# boxer_rpi.net
KiCad netlist of a schematic drawn in Altium Designer
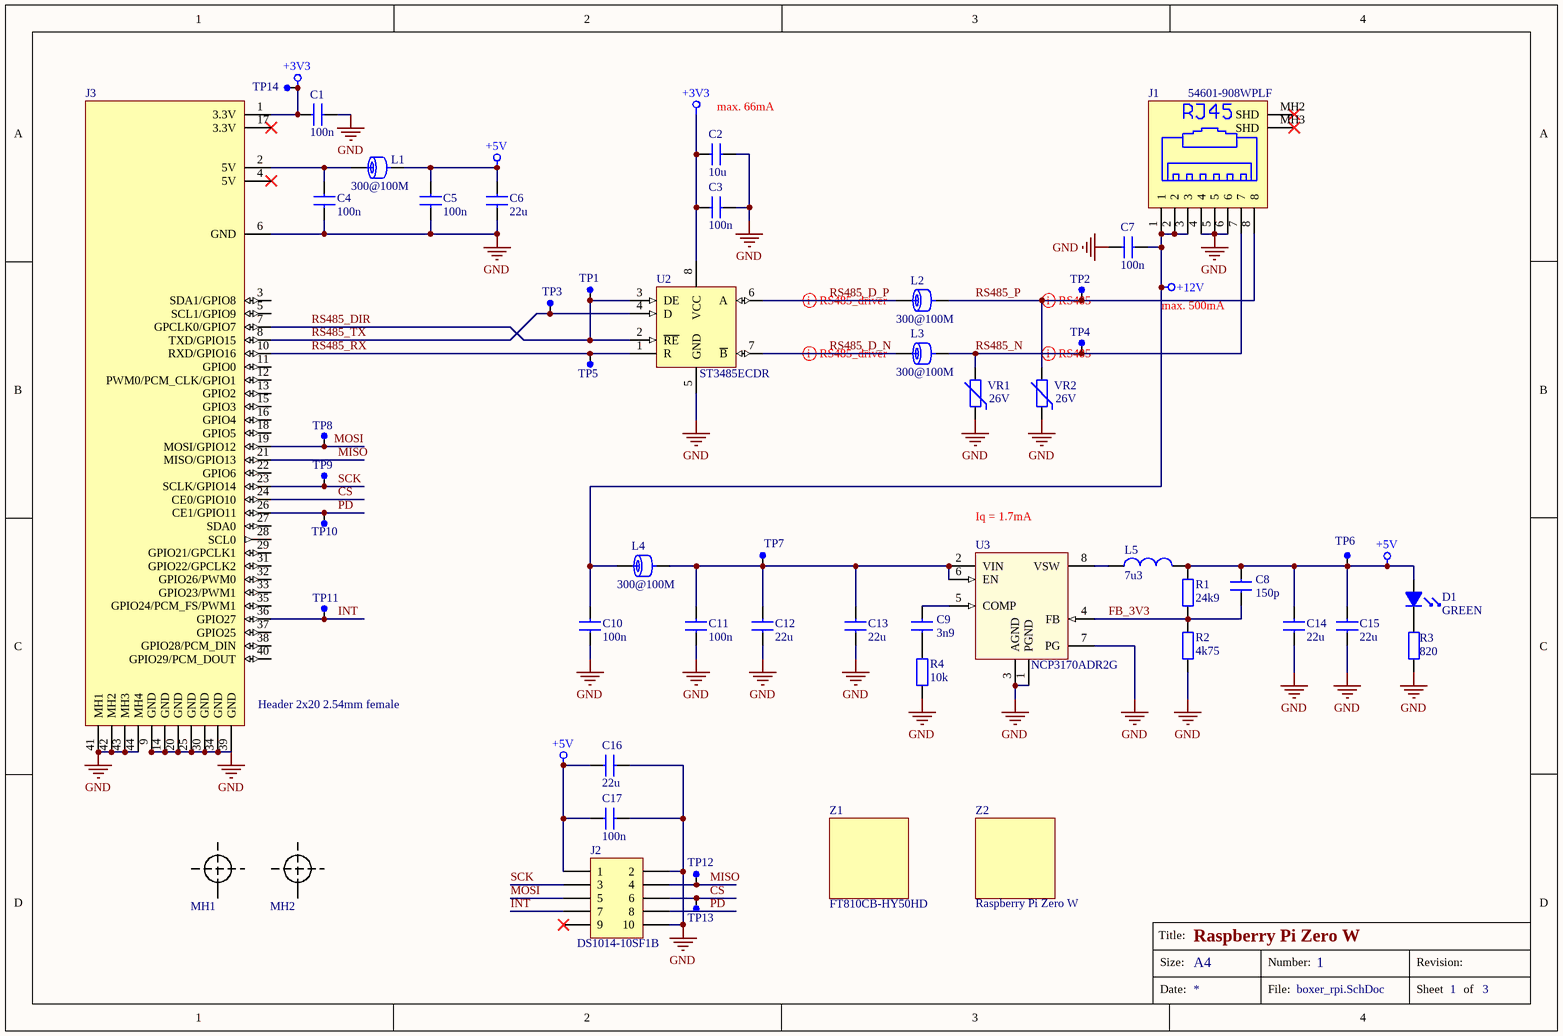
[diagram p0: boxer_rpi.SchDoc]

(export (version "E")
  (design (tool "Eeschema 10.0.6"))
  (components
    (comp (ref "C1")
      (value "100n")
      (footprint "C_0805")
      (description "Capacitor")
      (libsource (lib "boxer_pas") (part "Capacitor"))
    )
    (comp (ref "C2")
      (value "10u")
      (footprint "C_1206")
      (description "Capacitor")
      (fields (field (name "Comment") "TME: CL31A226MOCLNNC"))
      (libsource (lib "boxer_pas") (part "Capacitor"))
    )
    (comp (ref "C3")
      (value "100n")
      (footprint "C_0805")
      (description "Capacitor")
      (libsource (lib "boxer_pas") (part "Capacitor"))
    )
    (comp (ref "C4")
      (value "100n")
      (footprint "C_0805")
      (description "Capacitor")
      (libsource (lib "boxer_pas") (part "Capacitor"))
    )
    (comp (ref "C5")
      (value "100n")
      (footprint "C_0805")
      (description "Capacitor")
      (libsource (lib "boxer_pas") (part "Capacitor"))
    )
    (comp (ref "C6")
      (value "22u")
      (footprint "C_1206")
      (description "Capacitor")
      (fields (field (name "Comment") "TME: CL31A226MOCLNNC"))
      (libsource (lib "boxer_pas") (part "Capacitor"))
    )
    (comp (ref "C7")
      (value "100n")
      (footprint "C_0805")
      (description "Capacitor")
      (libsource (lib "boxer_pas") (part "Capacitor"))
    )
    (comp (ref "C8")
      (value "150p")
      (footprint "C_0805")
      (description "Capacitor")
      (fields (field (name "Comment") "885012207081"))
      (libsource (lib "boxer_pas") (part "Capacitor"))
    )
    (comp (ref "C9")
      (value "3n9")
      (footprint "C_0805")
      (description "Capacitor")
      (fields (field (name "Comment") "885012207089"))
      (libsource (lib "boxer_pas") (part "Capacitor"))
    )
    (comp (ref "C10")
      (value "100n")
      (footprint "C_0805")
      (description "Capacitor")
      (libsource (lib "boxer_pas") (part "Capacitor"))
    )
    (comp (ref "C11")
      (value "100n")
      (footprint "C_0805")
      (description "Capacitor")
      (libsource (lib "boxer_pas") (part "Capacitor"))
    )
    (comp (ref "C12")
      (value "22u")
      (footprint "C_1206")
      (description "Capacitor")
      (fields (field (name "Comment") "TME: CL31A226MOCLNNC"))
      (libsource (lib "boxer_pas") (part "Capacitor"))
    )
    (comp (ref "C13")
      (value "22u")
      (footprint "C_1206")
      (description "Capacitor")
      (fields (field (name "Comment") "TME: CL31A226MOCLNNC"))
      (libsource (lib "boxer_pas") (part "Capacitor"))
    )
    (comp (ref "C14")
      (value "22u")
      (footprint "C_1206")
      (description "Capacitor")
      (fields (field (name "Comment") "TME: CL31A226MOCLNNC"))
      (libsource (lib "boxer_pas") (part "Capacitor"))
    )
    (comp (ref "C15")
      (value "22u")
      (footprint "C_1206")
      (description "Capacitor")
      (fields (field (name "Comment") "TME: CL31A226MOCLNNC"))
      (libsource (lib "boxer_pas") (part "Capacitor"))
    )
    (comp (ref "C16")
      (value "22u")
      (footprint "C_1206")
      (description "Capacitor")
      (fields (field (name "Comment") "TME: CL31A226MOCLNNC"))
      (libsource (lib "boxer_pas") (part "Capacitor"))
    )
    (comp (ref "C17")
      (value "100n")
      (footprint "C_0805")
      (description "Capacitor")
      (libsource (lib "boxer_pas") (part "Capacitor"))
    )
    (comp (ref "D1")
      (value "GREEN")
      (footprint "LED_0805")
      (description "Typical RED, GREEN, YELLOW, AMBER GaAs LED")
      (fields (field (name "Comment") "KP-2012LSGC"))
      (libsource (lib "altium-import") (part "root_3_LED_"))
    )
    (comp (ref "J1")
      (value "54601-908WPLF")
      (footprint "RJ45_54601-908WPLF")
      (description "RJ45 Socket, 8pin, No Key, Molex MX-95001-2881")
      (libsource (lib "boxer_mechanical") (part "RJ45-8"))
    )
    (comp (ref "J2")
      (value "DS1014-10SF1B")
      (footprint "215307-5")
      (description "Header, 5-Pin, Dual row")
      (fields (field (name "Comment") "Header 5X2"))
      (libsource (lib "boxer_mechanical") (part "Header 5X2"))
    )
    (comp (ref "J3")
      (value "Header 2x20 2.54mm female")
      (footprint "Header RPI0")
      (fields (field (name "Comment") "Header RPi Zero W"))
      (libsource (lib "boxer_mechanical") (part "Header RPI0"))
    )
    (comp (ref "L1")
      (value "300@100M")
      (footprint "L_0805")
      (description "Ferrite Bead")
      (fields (field (name "Comment") "742792031"))
      (libsource (lib "boxer_pas") (part "FB"))
    )
    (comp (ref "L2")
      (value "300@100M")
      (footprint "L_0805")
      (description "Ferrite Bead")
      (fields (field (name "Comment") "742792031"))
      (libsource (lib "boxer_pas") (part "FB"))
    )
    (comp (ref "L3")
      (value "300@100M")
      (footprint "L_0805")
      (description "Ferrite Bead")
      (fields (field (name "Comment") "742792031"))
      (libsource (lib "boxer_pas") (part "FB"))
    )
    (comp (ref "L4")
      (value "300@100M")
      (footprint "L_0805")
      (description "Ferrite Bead")
      (fields (field (name "Comment") "742792031"))
      (libsource (lib "boxer_pas") (part "FB"))
    )
    (comp (ref "L5")
      (value "7u3")
      (footprint "L_6.7x6.7mm")
      (description "FIXED IND 7.3UH 2.1A 54 MOHM SMD")
      (fields (field (name "Comment") "308-1500-1-ND"))
      (libsource (lib "boxer_pas") (part "Inductor"))
    )
    (comp (ref "MH1")
      (value "Mounting hole")
      (footprint "MH_M3")
      (libsource (lib "boxer_mechanical") (part "Mounting hole"))
    )
    (comp (ref "MH2")
      (value "Mounting hole")
      (footprint "MH_M3")
      (libsource (lib "boxer_mechanical") (part "Mounting hole"))
    )
    (comp (ref "R1")
      (value "24k9")
      (footprint "R_0805")
      (description "Resistor")
      (fields (field (name "Comment") "RNCP0805FTD24K9"))
      (libsource (lib "boxer_pas") (part "Resistor"))
    )
    (comp (ref "R2")
      (value "4k75")
      (footprint "R_0805")
      (description "Resistor")
      (fields (field (name "Comment") "RNCP0805FTD4K75"))
      (libsource (lib "boxer_pas") (part "Resistor"))
    )
    (comp (ref "R3")
      (value "820")
      (footprint "R_0805")
      (description "Resistor")
      (libsource (lib "altium-import") (part "root_1_Resistor_"))
    )
    (comp (ref "R4")
      (value "10k")
      (footprint "R_1206")
      (description "Resistor")
      (libsource (lib "boxer_pas") (part "Resistor"))
    )
    (comp (ref "TP1")
      (value "TEST PAD")
      (footprint "PIN")
      (description "PAD 1.5mm")
      (libsource (lib "boxer_mechanical") (part "TEST_PAD"))
    )
    (comp (ref "TP2")
      (value "TEST PAD")
      (footprint "PIN")
      (description "PAD 1.5mm")
      (libsource (lib "boxer_mechanical") (part "TEST_PAD"))
    )
    (comp (ref "TP3")
      (value "TEST PAD")
      (footprint "PIN")
      (description "PAD 1.5mm")
      (libsource (lib "boxer_mechanical") (part "TEST_PAD"))
    )
    (comp (ref "TP4")
      (value "TEST PAD")
      (footprint "PIN")
      (description "PAD 1.5mm")
      (libsource (lib "boxer_mechanical") (part "TEST_PAD"))
    )
    (comp (ref "TP5")
      (value "TEST PAD")
      (footprint "PIN")
      (description "PAD 1.5mm")
      (libsource (lib "boxer_mechanical") (part "TEST_PAD"))
    )
    (comp (ref "TP6")
      (value "TEST PAD")
      (footprint "PIN")
      (description "PAD 1.5mm")
      (libsource (lib "boxer_mechanical") (part "TEST_PAD"))
    )
    (comp (ref "TP7")
      (value "TEST PAD")
      (footprint "PIN")
      (description "PAD 1.5mm")
      (libsource (lib "boxer_mechanical") (part "TEST_PAD"))
    )
    (comp (ref "TP8")
      (value "TEST PAD")
      (footprint "PIN")
      (description "PAD 1.5mm")
      (libsource (lib "boxer_mechanical") (part "TEST_PAD"))
    )
    (comp (ref "TP9")
      (value "TEST PAD")
      (footprint "PIN")
      (description "PAD 1.5mm")
      (libsource (lib "boxer_mechanical") (part "TEST_PAD"))
    )
    (comp (ref "TP10")
      (value "TEST PAD")
      (footprint "PIN")
      (description "PAD 1.5mm")
      (libsource (lib "boxer_mechanical") (part "TEST_PAD"))
    )
    (comp (ref "TP11")
      (value "TEST PAD")
      (footprint "PIN")
      (description "PAD 1.5mm")
      (libsource (lib "boxer_mechanical") (part "TEST_PAD"))
    )
    (comp (ref "TP12")
      (value "TEST PAD")
      (footprint "PIN")
      (description "PAD 1.5mm")
      (libsource (lib "boxer_mechanical") (part "TEST_PAD"))
    )
    (comp (ref "TP13")
      (value "TEST PAD")
      (footprint "PIN")
      (description "PAD 1.5mm")
      (libsource (lib "boxer_mechanical") (part "TEST_PAD"))
    )
    (comp (ref "TP14")
      (value "TEST PAD")
      (footprint "PIN")
      (description "PAD 1.5mm")
      (libsource (lib "boxer_mechanical") (part "TEST_PAD"))
    )
    (comp (ref "U2")
      (value "ST3485ECDR")
      (footprint "SO8")
      (description "RS-422/RS-485 Interface IC Hi-Spd Lo Pwr Trans")
      (libsource (lib "boxer_ic") (part "ST485BDR"))
    )
    (comp (ref "U3")
      (value "NCP3170ADR2G")
      (footprint "SO8")
      (description "Synchronous PWM Switching Converter")
      (libsource (lib "boxer_ic") (part "NCP3170"))
    )
    (comp (ref "VR1")
      (value "26V")
      (footprint "VR_0805")
      (description "34.5V 20A Varistor 1 Circuit Surface Mount, MLCV 0805 (2012 Metric)")
      (fields (field (name "Comment") "AMCV-0805-260-C800N-T"))
      (libsource (lib "boxer_pas") (part "Varistor"))
    )
    (comp (ref "VR2")
      (value "26V")
      (footprint "VR_0805")
      (description "34.5V 20A Varistor 1 Circuit Surface Mount, MLCV 0805 (2012 Metric)")
      (fields (field (name "Comment") "AMCV-0805-260-C800N-T"))
      (libsource (lib "boxer_pas") (part "Varistor"))
    )
    (comp (ref "Z1")
      (value "FT810CB-HY50HD")
      (footprint "FT810CB-HY50HD")
      (libsource (lib "boxer_ic") (part "FT810CB-HY50HD"))
    )
    (comp (ref "Z2")
      (value "Raspberry Pi Zero W")
      (footprint "RPI_ZERO")
      (libsource (lib "boxer_ic") (part "RPi Zero W"))
    )
  )
  (nets
    (net (code "1") (name "+3V3") (class "Default")
      (node (ref "C1") (pin "2") (pinfunction "2_2") (pintype "passive"))
      (node (ref "C2") (pin "2") (pinfunction "2_2") (pintype "passive"))
      (node (ref "C3") (pin "1") (pinfunction "1_1") (pintype "passive"))
      (node (ref "J3") (pin "1") (pinfunction "3.3V_1") (pintype "power_in"))
      (node (ref "TP14") (pin "1") (pinfunction "1_1") (pintype "passive"))
      (node (ref "U2") (pin "8") (pinfunction "VCC_8") (pintype "power_in"))
    )
    (net (code "2") (name "+5V") (class "Default")
      (node (ref "C14") (pin "2") (pinfunction "2_2") (pintype "passive"))
      (node (ref "C15") (pin "2") (pinfunction "2_2") (pintype "passive"))
      (node (ref "C16") (pin "2") (pinfunction "2_2") (pintype "passive"))
      (node (ref "C17") (pin "2") (pinfunction "2_2") (pintype "passive"))
      (node (ref "C5") (pin "1") (pinfunction "1_1") (pintype "passive"))
      (node (ref "C6") (pin "2") (pinfunction "2_2") (pintype "passive"))
      (node (ref "C8") (pin "2") (pinfunction "2_2") (pintype "passive"))
      (node (ref "D1") (pin "1") (pinfunction "A_1") (pintype "passive"))
      (node (ref "J2") (pin "1") (pinfunction "1_1") (pintype "passive"))
      (node (ref "L1") (pin "2") (pinfunction "2_2") (pintype "passive"))
      (node (ref "L5") (pin "2") (pinfunction "2_2") (pintype "passive"))
      (node (ref "R1") (pin "2") (pinfunction "2_2") (pintype "passive"))
      (node (ref "TP6") (pin "1") (pinfunction "1_1") (pintype "passive"))
    )
    (net (code "3") (name "+12V") (class "Default")
      (node (ref "C10") (pin "2") (pinfunction "2_2") (pintype "passive"))
      (node (ref "C7") (pin "1") (pinfunction "1_1") (pintype "passive"))
      (node (ref "J1") (pin "1") (pinfunction "1_1") (pintype "passive"))
      (node (ref "J1") (pin "2") (pinfunction "2_2") (pintype "passive"))
      (node (ref "J1") (pin "3") (pinfunction "3_3") (pintype "passive"))
      (node (ref "L4") (pin "1") (pinfunction "1_1") (pintype "passive"))
    )
    (net (code "4") (name "/CS") (class "Default")
      (node (ref "J2") (pin "6") (pinfunction "6_6") (pintype "passive"))
      (node (ref "J3") (pin "24") (pinfunction "CE0/GPIO10_24") (pintype "bidirectional"))
      (node (ref "TP13") (pin "1") (pinfunction "1_1") (pintype "passive"))
    )
    (net (code "5") (name "/FB_3V3") (class "Default")
      (node (ref "C8") (pin "1") (pinfunction "1_1") (pintype "passive"))
      (node (ref "R1") (pin "1") (pinfunction "1_1") (pintype "passive"))
      (node (ref "R2") (pin "2") (pinfunction "2_2") (pintype "passive"))
      (node (ref "U3") (pin "4") (pinfunction "FB_4") (pintype "input"))
    )
    (net (code "6") (name "/INT") (class "Default")
      (node (ref "J2") (pin "7") (pinfunction "7_7") (pintype "passive"))
      (node (ref "J3") (pin "36") (pinfunction "GPIO27_36") (pintype "bidirectional"))
      (node (ref "TP11") (pin "1") (pinfunction "1_1") (pintype "passive"))
    )
    (net (code "7") (name "/MISO") (class "Default")
      (node (ref "J2") (pin "4") (pinfunction "4_4") (pintype "passive"))
      (node (ref "J3") (pin "21") (pinfunction "MISO/GPIO13_21") (pintype "bidirectional"))
      (node (ref "TP12") (pin "1") (pinfunction "1_1") (pintype "passive"))
    )
    (net (code "8") (name "/MOSI") (class "Default")
      (node (ref "J2") (pin "5") (pinfunction "5_5") (pintype "passive"))
      (node (ref "J3") (pin "19") (pinfunction "MOSI/GPIO12_19") (pintype "bidirectional"))
      (node (ref "TP8") (pin "1") (pinfunction "1_1") (pintype "passive"))
    )
    (net (code "9") (name "/PD") (class "Default")
      (node (ref "J2") (pin "8") (pinfunction "8_8") (pintype "passive"))
      (node (ref "J3") (pin "26") (pinfunction "CE1/GPIO11_26") (pintype "bidirectional"))
      (node (ref "TP10") (pin "1") (pinfunction "1_1") (pintype "passive"))
    )
    (net (code "10") (name "/RS485_DIR") (class "Default")
      (node (ref "J3") (pin "7") (pinfunction "GPCLK0/GPIO7_7") (pintype "bidirectional"))
      (node (ref "TP1") (pin "1") (pinfunction "1_1") (pintype "passive"))
      (node (ref "U2") (pin "2") (pinfunction "~{RE}_2") (pintype "input"))
      (node (ref "U2") (pin "3") (pinfunction "DE_3") (pintype "input"))
    )
    (net (code "11") (name "/RS485_D_N") (class "Default")
      (node (ref "L3") (pin "1") (pinfunction "1_1") (pintype "passive"))
      (node (ref "U2") (pin "7") (pinfunction "~{B}_7") (pintype "bidirectional"))
    )
    (net (code "12") (name "/RS485_D_P") (class "Default")
      (node (ref "L2") (pin "1") (pinfunction "1_1") (pintype "passive"))
      (node (ref "U2") (pin "6") (pinfunction "A_6") (pintype "bidirectional"))
    )
    (net (code "13") (name "/RS485_N") (class "Default")
      (node (ref "J1") (pin "7") (pinfunction "7_7") (pintype "passive"))
      (node (ref "L3") (pin "2") (pinfunction "2_2") (pintype "passive"))
      (node (ref "TP4") (pin "1") (pinfunction "1_1") (pintype "passive"))
      (node (ref "VR1") (pin "1") (pinfunction "1_1") (pintype "passive"))
    )
    (net (code "14") (name "/RS485_P") (class "Default")
      (node (ref "J1") (pin "8") (pinfunction "8_8") (pintype "passive"))
      (node (ref "L2") (pin "2") (pinfunction "2_2") (pintype "passive"))
      (node (ref "TP2") (pin "1") (pinfunction "1_1") (pintype "passive"))
      (node (ref "VR2") (pin "1") (pinfunction "1_1") (pintype "passive"))
    )
    (net (code "15") (name "/RS485_RX") (class "Default")
      (node (ref "J3") (pin "10") (pinfunction "RXD/GPIO16_10") (pintype "bidirectional"))
      (node (ref "TP5") (pin "1") (pinfunction "1_1") (pintype "passive"))
      (node (ref "U2") (pin "1") (pinfunction "R_1") (pintype "tri_state"))
    )
    (net (code "16") (name "/RS485_TX") (class "Default")
      (node (ref "J3") (pin "8") (pinfunction "TXD/GPIO15_8") (pintype "bidirectional"))
      (node (ref "TP3") (pin "1") (pinfunction "1_1") (pintype "passive"))
      (node (ref "U2") (pin "4") (pinfunction "D_4") (pintype "input"))
    )
    (net (code "17") (name "/SCK") (class "Default")
      (node (ref "J2") (pin "3") (pinfunction "3_3") (pintype "passive"))
      (node (ref "J3") (pin "23") (pinfunction "SCLK/GPIO14_23") (pintype "bidirectional"))
      (node (ref "TP9") (pin "1") (pinfunction "1_1") (pintype "passive"))
    )
    (net (code "18") (name "GND") (class "Default")
      (node (ref "C1") (pin "1") (pinfunction "1_1") (pintype "passive"))
      (node (ref "C10") (pin "1") (pinfunction "1_1") (pintype "passive"))
      (node (ref "C11") (pin "1") (pinfunction "1_1") (pintype "passive"))
      (node (ref "C12") (pin "1") (pinfunction "1_1") (pintype "passive"))
      (node (ref "C13") (pin "1") (pinfunction "1_1") (pintype "passive"))
      (node (ref "C14") (pin "1") (pinfunction "1_1") (pintype "passive"))
      (node (ref "C15") (pin "1") (pinfunction "1_1") (pintype "passive"))
      (node (ref "C16") (pin "1") (pinfunction "1_1") (pintype "passive"))
      (node (ref "C17") (pin "1") (pinfunction "1_1") (pintype "passive"))
      (node (ref "C2") (pin "1") (pinfunction "1_1") (pintype "passive"))
      (node (ref "C3") (pin "2") (pinfunction "2_2") (pintype "passive"))
      (node (ref "C4") (pin "2") (pinfunction "2_2") (pintype "passive"))
      (node (ref "C5") (pin "2") (pinfunction "2_2") (pintype "passive"))
      (node (ref "C6") (pin "1") (pinfunction "1_1") (pintype "passive"))
      (node (ref "C7") (pin "2") (pinfunction "2_2") (pintype "passive"))
      (node (ref "J1") (pin "4") (pinfunction "4_4") (pintype "passive"))
      (node (ref "J1") (pin "5") (pinfunction "5_5") (pintype "passive"))
      (node (ref "J1") (pin "6") (pinfunction "6_6") (pintype "passive"))
      (node (ref "J2") (pin "10") (pinfunction "10_10") (pintype "passive"))
      (node (ref "J2") (pin "2") (pinfunction "2_2") (pintype "passive"))
      (node (ref "J3") (pin "14") (pinfunction "GND_14") (pintype "power_in"))
      (node (ref "J3") (pin "20") (pinfunction "GND_20") (pintype "power_in"))
      (node (ref "J3") (pin "25") (pinfunction "GND_25") (pintype "power_in"))
      (node (ref "J3") (pin "30") (pinfunction "GND_30") (pintype "power_in"))
      (node (ref "J3") (pin "34") (pinfunction "GND_34") (pintype "power_in"))
      (node (ref "J3") (pin "39") (pinfunction "GND_39") (pintype "power_in"))
      (node (ref "J3") (pin "41") (pinfunction "MH1_41") (pintype "passive"))
      (node (ref "J3") (pin "42") (pinfunction "MH2_42") (pintype "passive"))
      (node (ref "J3") (pin "43") (pinfunction "MH3_43") (pintype "passive"))
      (node (ref "J3") (pin "44") (pinfunction "MH4_44") (pintype "passive"))
      (node (ref "J3") (pin "6") (pinfunction "GND_6") (pintype "power_in"))
      (node (ref "J3") (pin "9") (pinfunction "GND_9") (pintype "power_in"))
      (node (ref "R2") (pin "1") (pinfunction "1_1") (pintype "passive"))
      (node (ref "R3") (pin "1") (pinfunction "1_1") (pintype "passive"))
      (node (ref "R4") (pin "1") (pinfunction "1_1") (pintype "passive"))
      (node (ref "U2") (pin "5") (pinfunction "GND_5") (pintype "power_in"))
      (node (ref "U3") (pin "1") (pinfunction "PGND_1") (pintype "power_in"))
      (node (ref "U3") (pin "3") (pinfunction "AGND_3") (pintype "power_in"))
      (node (ref "U3") (pin "7") (pinfunction "PG_7") (pintype "passive"))
      (node (ref "VR1") (pin "2") (pinfunction "2_2") (pintype "passive"))
      (node (ref "VR2") (pin "2") (pinfunction "2_2") (pintype "passive"))
    )
    (net (code "19") (name "Net-(C4-Pad1)") (class "Default")
      (node (ref "C4") (pin "1") (pinfunction "1_1") (pintype "passive"))
      (node (ref "J3") (pin "2") (pinfunction "5V_2") (pintype "power_in"))
      (node (ref "L1") (pin "1") (pinfunction "1_1") (pintype "passive"))
    )
    (net (code "20") (name "Net-(C9-Pad1)") (class "Default")
      (node (ref "C9") (pin "1") (pinfunction "1_1") (pintype "passive"))
      (node (ref "R4") (pin "2") (pinfunction "2_2") (pintype "passive"))
    )
    (net (code "21") (name "Net-(D1-K)") (class "Default")
      (node (ref "D1") (pin "2") (pinfunction "K_2") (pintype "passive"))
      (node (ref "R3") (pin "2") (pinfunction "2_2") (pintype "passive"))
    )
    (net (code "22") (name "Net-(U3-COMP)") (class "Default")
      (node (ref "C9") (pin "2") (pinfunction "2_2") (pintype "passive"))
      (node (ref "U3") (pin "5") (pinfunction "COMP_5") (pintype "input"))
    )
    (net (code "23") (name "Net-(U3-EN)") (class "Default")
      (node (ref "C11") (pin "2") (pinfunction "2_2") (pintype "passive"))
      (node (ref "C12") (pin "2") (pinfunction "2_2") (pintype "passive"))
      (node (ref "C13") (pin "2") (pinfunction "2_2") (pintype "passive"))
      (node (ref "L4") (pin "2") (pinfunction "2_2") (pintype "passive"))
      (node (ref "TP7") (pin "1") (pinfunction "1_1") (pintype "passive"))
      (node (ref "U3") (pin "2") (pinfunction "VIN_2") (pintype "power_in"))
      (node (ref "U3") (pin "6") (pinfunction "EN_6") (pintype "input"))
    )
    (net (code "24") (name "Net-(U3-VSW)") (class "Default")
      (node (ref "L5") (pin "1") (pinfunction "1_1") (pintype "passive"))
      (node (ref "U3") (pin "8") (pinfunction "VSW_8") (pintype "power_in"))
    )
    (net (code "25") (name "unconnected-(J1-SHD-PadMH2)") (class "Default")
      (node (ref "J1") (pin "MH2") (pinfunction "SHD_MH2") (pintype "passive+no_connect"))
    )
    (net (code "26") (name "unconnected-(J1-SHD-PadMH3)") (class "Default")
      (node (ref "J1") (pin "MH3") (pinfunction "SHD_MH3") (pintype "passive+no_connect"))
    )
    (net (code "27") (name "unconnected-(J2-Pad9)") (class "Default")
      (node (ref "J2") (pin "9") (pinfunction "9_9") (pintype "passive+no_connect"))
    )
    (net (code "28") (name "unconnected-(J3-3.3V-Pad17)") (class "Default")
      (node (ref "J3") (pin "17") (pinfunction "3.3V_17") (pintype "power_in+no_connect"))
    )
    (net (code "29") (name "unconnected-(J3-5V-Pad4)") (class "Default")
      (node (ref "J3") (pin "4") (pinfunction "5V_4") (pintype "power_in+no_connect"))
    )
    (net (code "30") (name "unconnected-(J3-GPIO0-Pad11)") (class "Default")
      (node (ref "J3") (pin "11") (pinfunction "GPIO0_11") (pintype "bidirectional"))
    )
    (net (code "31") (name "unconnected-(J3-GPIO2-Pad13)") (class "Default")
      (node (ref "J3") (pin "13") (pinfunction "GPIO2_13") (pintype "bidirectional"))
    )
    (net (code "32") (name "unconnected-(J3-GPIO3-Pad15)") (class "Default")
      (node (ref "J3") (pin "15") (pinfunction "GPIO3_15") (pintype "bidirectional"))
    )
    (net (code "33") (name "unconnected-(J3-GPIO4-Pad16)") (class "Default")
      (node (ref "J3") (pin "16") (pinfunction "GPIO4_16") (pintype "bidirectional"))
    )
    (net (code "34") (name "unconnected-(J3-GPIO5-Pad18)") (class "Default")
      (node (ref "J3") (pin "18") (pinfunction "GPIO5_18") (pintype "bidirectional"))
    )
    (net (code "35") (name "unconnected-(J3-GPIO6-Pad22)") (class "Default")
      (node (ref "J3") (pin "22") (pinfunction "GPIO6_22") (pintype "bidirectional"))
    )
    (net (code "36") (name "unconnected-(J3-GPIO21{slash}GPCLK1-Pad29)") (class "Default")
      (node (ref "J3") (pin "29") (pinfunction "GPIO21/GPCLK1_29") (pintype "bidirectional"))
    )
    (net (code "37") (name "unconnected-(J3-GPIO22{slash}GPCLK2-Pad31)") (class "Default")
      (node (ref "J3") (pin "31") (pinfunction "GPIO22/GPCLK2_31") (pintype "bidirectional"))
    )
    (net (code "38") (name "unconnected-(J3-GPIO23{slash}PWM1-Pad33)") (class "Default")
      (node (ref "J3") (pin "33") (pinfunction "GPIO23/PWM1_33") (pintype "bidirectional"))
    )
    (net (code "39") (name "unconnected-(J3-GPIO24{slash}PCM_FS{slash}PWM1-Pad35)") (class "Default")
      (node (ref "J3") (pin "35") (pinfunction "GPIO24/PCM_FS/PWM1_35") (pintype "bidirectional"))
    )
    (net (code "40") (name "unconnected-(J3-GPIO25-Pad37)") (class "Default")
      (node (ref "J3") (pin "37") (pinfunction "GPIO25_37") (pintype "bidirectional"))
    )
    (net (code "41") (name "unconnected-(J3-GPIO26{slash}PWM0-Pad32)") (class "Default")
      (node (ref "J3") (pin "32") (pinfunction "GPIO26/PWM0_32") (pintype "bidirectional"))
    )
    (net (code "42") (name "unconnected-(J3-GPIO28{slash}PCM_DIN-Pad38)") (class "Default")
      (node (ref "J3") (pin "38") (pinfunction "GPIO28/PCM_DIN_38") (pintype "bidirectional"))
    )
    (net (code "43") (name "unconnected-(J3-GPIO29{slash}PCM_DOUT-Pad40)") (class "Default")
      (node (ref "J3") (pin "40") (pinfunction "GPIO29/PCM_DOUT_40") (pintype "bidirectional"))
    )
    (net (code "44") (name "unconnected-(J3-PWM0{slash}PCM_CLK{slash}GPIO1-Pad12)") (class "Default")
      (node (ref "J3") (pin "12") (pinfunction "PWM0/PCM_CLK/GPIO1_12") (pintype "bidirectional"))
    )
    (net (code "45") (name "unconnected-(J3-SCL0-Pad28)") (class "Default")
      (node (ref "J3") (pin "28") (pinfunction "SCL0_28") (pintype "output"))
    )
    (net (code "46") (name "unconnected-(J3-SCL1{slash}GPIO9-Pad5)") (class "Default")
      (node (ref "J3") (pin "5") (pinfunction "SCL1/GPIO9_5") (pintype "bidirectional"))
    )
    (net (code "47") (name "unconnected-(J3-SDA0-Pad27)") (class "Default")
      (node (ref "J3") (pin "27") (pinfunction "SDA0_27") (pintype "bidirectional"))
    )
    (net (code "48") (name "unconnected-(J3-SDA1{slash}GPIO8-Pad3)") (class "Default")
      (node (ref "J3") (pin "3") (pinfunction "SDA1/GPIO8_3") (pintype "bidirectional"))
    )
    (net (code "49") (name "unconnected-(MH1-PadMH)") (class "Default")
      (node (ref "MH1") (pin "MH") (pinfunction "MH_MH") (pintype "passive"))
    )
    (net (code "50") (name "unconnected-(MH2-PadMH)") (class "Default")
      (node (ref "MH2") (pin "MH") (pinfunction "MH_MH") (pintype "passive"))
    )
  )
)
